# Main.net
KiCad netlist of a schematic drawn in Altium Designer
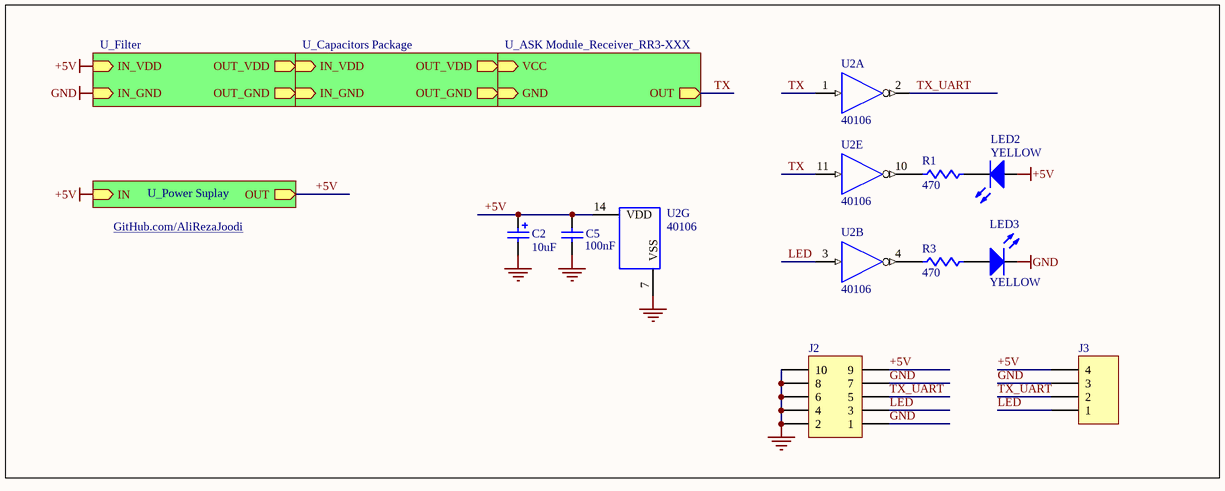
[diagram p0: Main.SchDoc]

(export (version "E")
  (design (tool "Eeschema 10.0.6"))
  (components
    (comp (ref "C2")
      (value "10uF")
      (footprint "CAPPR2.5-6.3x5")
      (description "Polarized Capacitor (Radial)")
      (fields (field (name "MANUFACTURER") "Generic Components") (field (name "PUBLISHER") "Altium Limited"))
      (libsource (lib "Miscellaneous Devices") (part "Cap Pol1"))
    )
    (comp (ref "C5")
      (value "100nF")
      (footprint "CAPNTO2.54-3.05x1.78A")
      (description "Capacitor")
      (fields (field (name "MANUFACTURER") "Generic Components") (field (name "PUBLISHER") "Altium Limited"))
      (libsource (lib "Miscellaneous Devices") (part "Cap"))
    )
    (comp (ref "J2")
      (value "Header 5X2")
      (footprint "FKV10SN")
      (description "Header, 5-Pin, Dual row")
      (fields (field (name "MANUFACTURER") "Generic Components") (field (name "PUBLISHER") "Altium Limited"))
      (libsource (lib "Miscellaneous Connectors") (part "Header 5X2"))
    )
    (comp (ref "J3")
      (value "3PIN")
      (footprint "HDR1X4")
      (description "Header, 4-Pin")
      (fields (field (name "MANUFACTURER") "Generic Components") (field (name "PUBLISHER") "Altium Limited"))
      (libsource (lib "Miscellaneous Connectors") (part "Header 4"))
    )
    (comp (ref "LED2")
      (value "YELLOW")
      (footprint "LED-5mm_Red")
      (description "Typical INFRARED GaAs LED")
      (fields (field (name "MANUFACTURER") "Generic Components") (field (name "PUBLISHER") "Altium Limited"))
      (libsource (lib "Miscellaneous Devices") (part "LED"))
    )
    (comp (ref "LED3")
      (value "YELLOW")
      (footprint "LED-5mm_Red")
      (description "Typical INFRARED GaAs LED")
      (fields (field (name "MANUFACTURER") "Generic Components") (field (name "PUBLISHER") "Altium Limited"))
      (libsource (lib "Miscellaneous Devices") (part "LED"))
    )
    (comp (ref "R1")
      (value "470")
      (footprint "AXIAL-0.4")
      (description "Resistor")
      (fields (field (name "MANUFACTURER") "Generic Components") (field (name "PUBLISHER") "Altium Limited"))
      (libsource (lib "Miscellaneous Devices") (part "Res1"))
    )
    (comp (ref "R3")
      (value "470")
      (footprint "AXIAL-0.4")
      (description "Resistor")
      (fields (field (name "MANUFACTURER") "Generic Components") (field (name "PUBLISHER") "Altium Limited"))
      (libsource (lib "Miscellaneous Devices") (part "Res1"))
    )
    (comp (ref "U2")
      (value "40106")
      (footprint "DIP14")
      (description "Hex inverting Schmitt trigger, 14-Pin")
      (fields (field (name "PUBLISHER") "Altium Limited"))
      (libsource (lib "my Libraries") (part "40106"))
    )
  )
  (nets
    (net (code "1") (name "+5V") (class "Default")
      (node (ref "C2") (pin "1") (pinfunction "1_1") (pintype "passive"))
      (node (ref "C5") (pin "2") (pinfunction "2_2") (pintype "passive"))
      (node (ref "J2") (pin "9") (pinfunction "9_9") (pintype "passive"))
      (node (ref "J3") (pin "4") (pinfunction "4_4") (pintype "passive"))
      (node (ref "LED2") (pin "1") (pinfunction "A_1") (pintype "passive"))
      (node (ref "U2") (pin "14") (pinfunction "VDD_14") (pintype "passive"))
    )
    (net (code "2") (name "/LED") (class "Default")
      (node (ref "J2") (pin "3") (pinfunction "3_3") (pintype "passive"))
      (node (ref "J3") (pin "1") (pinfunction "1_1") (pintype "passive"))
      (node (ref "U2") (pin "3") (pinfunction "I_3") (pintype "input"))
    )
    (net (code "7") (name "/TX") (class "Default")
      (node (ref "U2") (pin "1") (pinfunction "I_1") (pintype "input"))
      (node (ref "U2") (pin "11") (pinfunction "I_11") (pintype "input"))
    )
    (net (code "8") (name "/TX_UART") (class "Default")
      (node (ref "J2") (pin "5") (pinfunction "5_5") (pintype "passive"))
      (node (ref "J3") (pin "2") (pinfunction "2_2") (pintype "passive"))
      (node (ref "U2") (pin "2") (pinfunction "~{O}_2") (pintype "output"))
    )
    (net (code "9") (name "GND") (class "Default")
      (node (ref "C2") (pin "2") (pinfunction "2_2") (pintype "passive"))
      (node (ref "C5") (pin "1") (pinfunction "1_1") (pintype "passive"))
      (node (ref "J2") (pin "1") (pinfunction "1_1") (pintype "passive"))
      (node (ref "J2") (pin "10") (pinfunction "10_10") (pintype "passive"))
      (node (ref "J2") (pin "2") (pinfunction "2_2") (pintype "passive"))
      (node (ref "J2") (pin "4") (pinfunction "4_4") (pintype "passive"))
      (node (ref "J2") (pin "6") (pinfunction "6_6") (pintype "passive"))
      (node (ref "J2") (pin "7") (pinfunction "7_7") (pintype "passive"))
      (node (ref "J2") (pin "8") (pinfunction "8_8") (pintype "passive"))
      (node (ref "J3") (pin "3") (pinfunction "3_3") (pintype "passive"))
      (node (ref "LED3") (pin "2") (pinfunction "K_2") (pintype "passive"))
      (node (ref "U2") (pin "7") (pinfunction "VSS_7") (pintype "power_in"))
    )
    (net (code "10") (name "Net-(LED2-K)") (class "Default")
      (node (ref "LED2") (pin "2") (pinfunction "K_2") (pintype "passive"))
      (node (ref "R1") (pin "2") (pinfunction "2_2") (pintype "passive"))
    )
    (net (code "11") (name "Net-(LED3-A)") (class "Default")
      (node (ref "LED3") (pin "1") (pinfunction "A_1") (pintype "passive"))
      (node (ref "R3") (pin "2") (pinfunction "2_2") (pintype "passive"))
    )
    (net (code "12") (name "Net-(U2B-~{O})") (class "Default")
      (node (ref "R3") (pin "1") (pinfunction "1_1") (pintype "passive"))
      (node (ref "U2") (pin "4") (pinfunction "~{O}_4") (pintype "output"))
    )
    (net (code "13") (name "Net-(U2E-~{O})") (class "Default")
      (node (ref "R1") (pin "1") (pinfunction "1_1") (pintype "passive"))
      (node (ref "U2") (pin "10") (pinfunction "~{O}_10") (pintype "output"))
    )
  )
)
